# bandpass_40m_v4.net
KiCad netlist of a schematic drawn in EAGLE
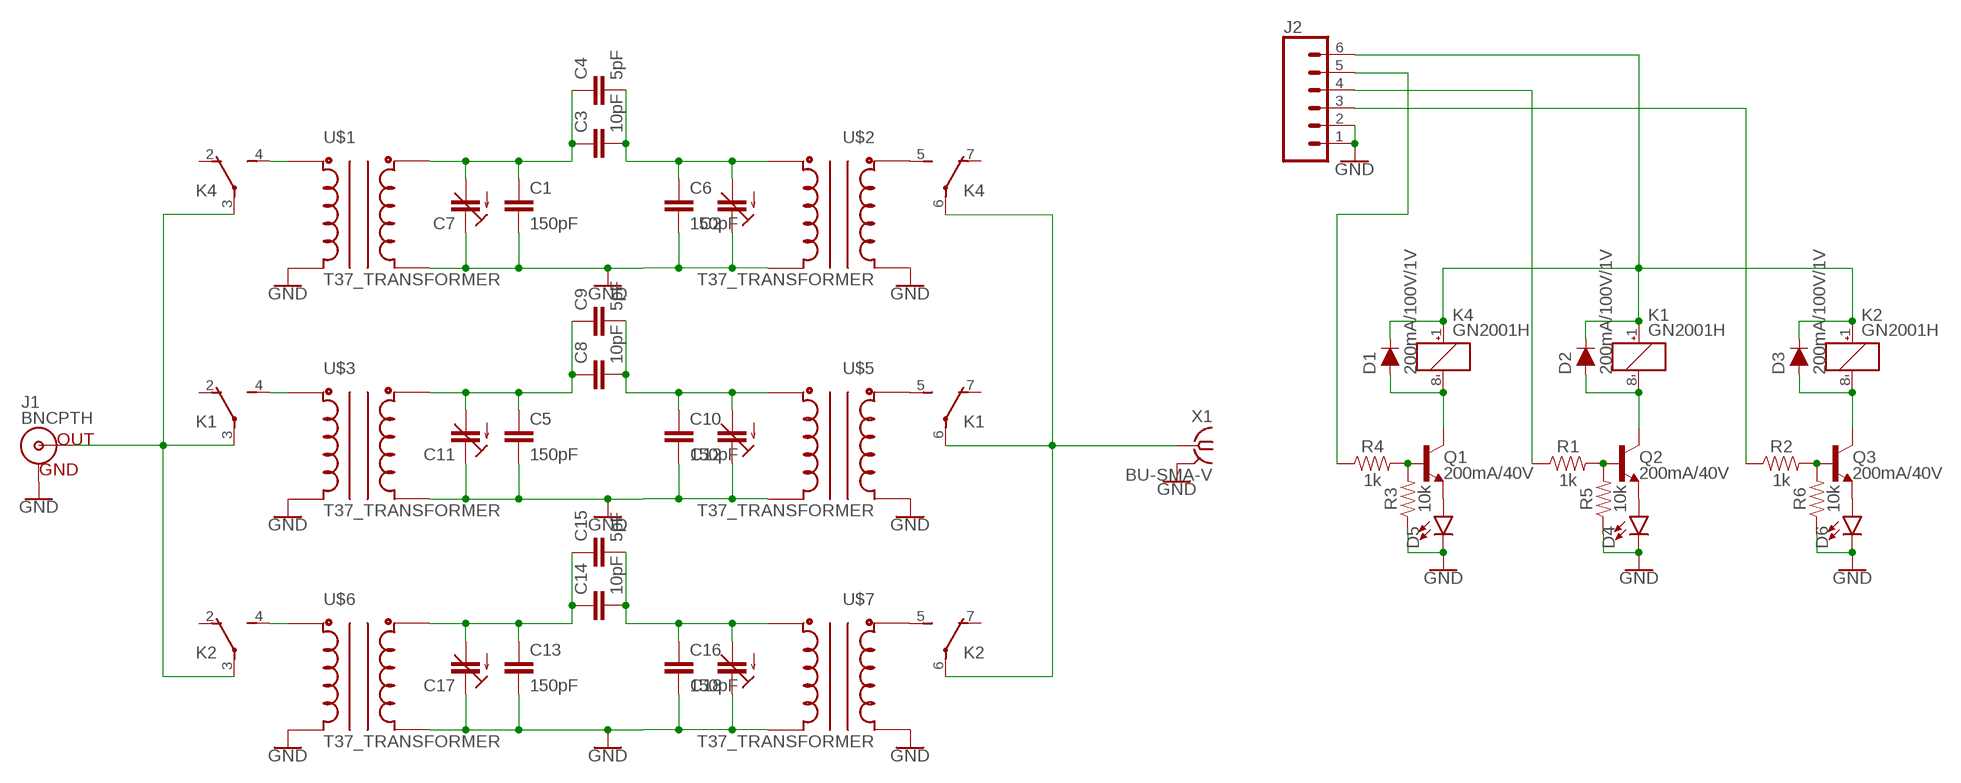
[diagram p0: schematic, sheet 1]

(export (version "E")
  (design (tool "Eeschema 10.0.6"))
  (components
    (comp (ref "C1")
      (value "150pF")
      (footprint "eagle-import:C5B3.5")
      (libsource (lib "eagle-import") (part "C5/3.5"))
    )
    (comp (ref "C2")
      (value "C-TRIMMTZ03")
      (footprint "eagle-import:CTRIMTZ03")
      (libsource (lib "eagle-import") (part "C-TRIMMTZ03"))
    )
    (comp (ref "C3")
      (value "10pF")
      (footprint "eagle-import:C5B3.5")
      (libsource (lib "eagle-import") (part "C5/3.5"))
    )
    (comp (ref "C4")
      (value "5pF")
      (footprint "eagle-import:C5B3.5")
      (libsource (lib "eagle-import") (part "C5/3.5"))
    )
    (comp (ref "C5")
      (value "150pF")
      (footprint "eagle-import:C5B3.5")
      (libsource (lib "eagle-import") (part "C5/3.5"))
    )
    (comp (ref "C6")
      (value "150pF")
      (footprint "eagle-import:C5B3.5")
      (libsource (lib "eagle-import") (part "C5/3.5"))
    )
    (comp (ref "C7")
      (value "C-TRIMMTZ03")
      (footprint "eagle-import:CTRIMTZ03")
      (libsource (lib "eagle-import") (part "C-TRIMMTZ03"))
    )
    (comp (ref "C8")
      (value "10pF")
      (footprint "eagle-import:C5B3.5")
      (libsource (lib "eagle-import") (part "C5/3.5"))
    )
    (comp (ref "C9")
      (value "5pF")
      (footprint "eagle-import:C5B3.5")
      (libsource (lib "eagle-import") (part "C5/3.5"))
    )
    (comp (ref "C10")
      (value "150pF")
      (footprint "eagle-import:C5B3.5")
      (libsource (lib "eagle-import") (part "C5/3.5"))
    )
    (comp (ref "C11")
      (value "C-TRIMMTZ03")
      (footprint "eagle-import:CTRIMTZ03")
      (libsource (lib "eagle-import") (part "C-TRIMMTZ03"))
    )
    (comp (ref "C12")
      (value "C-TRIMMTZ03")
      (footprint "eagle-import:CTRIMTZ03")
      (libsource (lib "eagle-import") (part "C-TRIMMTZ03"))
    )
    (comp (ref "C13")
      (value "150pF")
      (footprint "eagle-import:C5B3.5")
      (libsource (lib "eagle-import") (part "C5/3.5"))
    )
    (comp (ref "C14")
      (value "10pF")
      (footprint "eagle-import:C5B3.5")
      (libsource (lib "eagle-import") (part "C5/3.5"))
    )
    (comp (ref "C15")
      (value "5pF")
      (footprint "eagle-import:C5B3.5")
      (libsource (lib "eagle-import") (part "C5/3.5"))
    )
    (comp (ref "C16")
      (value "150pF")
      (footprint "eagle-import:C5B3.5")
      (libsource (lib "eagle-import") (part "C5/3.5"))
    )
    (comp (ref "C17")
      (value "C-TRIMMTZ03")
      (footprint "eagle-import:CTRIMTZ03")
      (libsource (lib "eagle-import") (part "C-TRIMMTZ03"))
    )
    (comp (ref "C18")
      (value "C-TRIMMTZ03")
      (footprint "eagle-import:CTRIMTZ03")
      (libsource (lib "eagle-import") (part "C-TRIMMTZ03"))
    )
    (comp (ref "D1")
      (value "200mA/100V/1V")
      (footprint "eagle-import:DIODE-1N4148")
      (libsource (lib "eagle-import") (part "DIODE-1N4148"))
    )
    (comp (ref "D2")
      (value "200mA/100V/1V")
      (footprint "eagle-import:DIODE-1N4148")
      (libsource (lib "eagle-import") (part "DIODE-1N4148"))
    )
    (comp (ref "D3")
      (value "200mA/100V/1V")
      (footprint "eagle-import:DIODE-1N4148")
      (libsource (lib "eagle-import") (part "DIODE-1N4148"))
    )
    (comp (ref "D4")
      (value "LED5MM")
      (footprint "eagle-import:LED_5MM")
      (libsource (lib "eagle-import") (part "LED5MM"))
    )
    (comp (ref "D5")
      (value "LED5MM")
      (footprint "eagle-import:LED_5MM")
      (libsource (lib "eagle-import") (part "LED5MM"))
    )
    (comp (ref "D6")
      (value "LED5MM")
      (footprint "eagle-import:LED_5MM")
      (libsource (lib "eagle-import") (part "LED5MM"))
    )
    (comp (ref "J1")
      (value "BNCPTH")
      (footprint "eagle-import:BNC")
      (libsource (lib "eagle-import") (part "BNCPTH"))
    )
    (comp (ref "J2")
      (value "CONN_06LONGPADS")
      (footprint "eagle-import:1X06_LONGPADS")
      (libsource (lib "eagle-import") (part "CONN_06LONGPADS"))
    )
    (comp (ref "K1")
      (value "GN2001H")
      (footprint "eagle-import:GN")
      (libsource (lib "eagle-import") (part "GN?2001H"))
    )
    (comp (ref "K2")
      (value "GN2001H")
      (footprint "eagle-import:GN")
      (libsource (lib "eagle-import") (part "GN?2001H"))
    )
    (comp (ref "K4")
      (value "GN2001H")
      (footprint "eagle-import:GN")
      (libsource (lib "eagle-import") (part "GN?2001H"))
    )
    (comp (ref "Q1")
      (value "200mA/40V")
      (footprint "eagle-import:TO-92")
      (libsource (lib "eagle-import") (part "TRANS_NPN-2N3904"))
    )
    (comp (ref "Q2")
      (value "200mA/40V")
      (footprint "eagle-import:TO-92")
      (libsource (lib "eagle-import") (part "TRANS_NPN-2N3904"))
    )
    (comp (ref "Q3")
      (value "200mA/40V")
      (footprint "eagle-import:TO-92")
      (libsource (lib "eagle-import") (part "TRANS_NPN-2N3904"))
    )
    (comp (ref "R1")
      (value "1k")
      (footprint "eagle-import:AXIAL-0.3")
      (libsource (lib "eagle-import") (part "1KOHM-HORIZ-1/4W-1%"))
    )
    (comp (ref "R2")
      (value "1k")
      (footprint "eagle-import:AXIAL-0.3")
      (libsource (lib "eagle-import") (part "1KOHM-HORIZ-1/4W-1%"))
    )
    (comp (ref "R3")
      (value "10k")
      (footprint "eagle-import:AXIAL-0.3")
      (libsource (lib "eagle-import") (part "1KOHM-HORIZ-1/4W-1%"))
    )
    (comp (ref "R4")
      (value "1k")
      (footprint "eagle-import:AXIAL-0.3")
      (libsource (lib "eagle-import") (part "1KOHM-HORIZ-1/4W-1%"))
    )
    (comp (ref "R5")
      (value "10k")
      (footprint "eagle-import:AXIAL-0.3")
      (libsource (lib "eagle-import") (part "1KOHM-HORIZ-1/4W-1%"))
    )
    (comp (ref "R6")
      (value "10k")
      (footprint "eagle-import:AXIAL-0.3")
      (libsource (lib "eagle-import") (part "1KOHM-HORIZ-1/4W-1%"))
    )
    (comp (ref "U$1")
      (value "T37_TRANSFORMER")
      (footprint "eagle-import:T37_TRANSFORMER")
      (libsource (lib "eagle-import") (part "T37_TRANSFORMER"))
    )
    (comp (ref "U$2")
      (value "T37_TRANSFORMER")
      (footprint "eagle-import:T37_TRANSFORMER")
      (libsource (lib "eagle-import") (part "T37_TRANSFORMER"))
    )
    (comp (ref "U$3")
      (value "T37_TRANSFORMER")
      (footprint "eagle-import:T37_TRANSFORMER")
      (libsource (lib "eagle-import") (part "T37_TRANSFORMER"))
    )
    (comp (ref "U$5")
      (value "T37_TRANSFORMER")
      (footprint "eagle-import:T37_TRANSFORMER")
      (libsource (lib "eagle-import") (part "T37_TRANSFORMER"))
    )
    (comp (ref "U$6")
      (value "T37_TRANSFORMER")
      (footprint "eagle-import:T37_TRANSFORMER")
      (libsource (lib "eagle-import") (part "T37_TRANSFORMER"))
    )
    (comp (ref "U$7")
      (value "T37_TRANSFORMER")
      (footprint "eagle-import:T37_TRANSFORMER")
      (libsource (lib "eagle-import") (part "T37_TRANSFORMER"))
    )
    (comp (ref "X1")
      (value "BU-SMA-V")
      (footprint "eagle-import:BU-SMA-V")
      (libsource (lib "eagle-import") (part "BU-SMA-V"))
    )
  )
  (nets
    (net (code "1") (name "GND") (class "Default")
      (node (ref "C1") (pin "2") (pinfunction "2_2") (pintype "passive"))
      (node (ref "C10") (pin "2") (pinfunction "2_2") (pintype "passive"))
      (node (ref "C11") (pin "1") (pinfunction "E_1") (pintype "passive"))
      (node (ref "C12") (pin "1") (pinfunction "E_1") (pintype "passive"))
      (node (ref "C13") (pin "2") (pinfunction "2_2") (pintype "passive"))
      (node (ref "C16") (pin "2") (pinfunction "2_2") (pintype "passive"))
      (node (ref "C17") (pin "1") (pinfunction "E_1") (pintype "passive"))
      (node (ref "C18") (pin "1") (pinfunction "E_1") (pintype "passive"))
      (node (ref "C2") (pin "1") (pinfunction "E_1") (pintype "passive"))
      (node (ref "C5") (pin "2") (pinfunction "2_2") (pintype "passive"))
      (node (ref "C6") (pin "2") (pinfunction "2_2") (pintype "passive"))
      (node (ref "C7") (pin "1") (pinfunction "E_1") (pintype "passive"))
      (node (ref "D4") (pin "K") (pinfunction "C_K") (pintype "passive"))
      (node (ref "D5") (pin "K") (pinfunction "C_K") (pintype "passive"))
      (node (ref "D6") (pin "K") (pinfunction "C_K") (pintype "passive"))
      (node (ref "J1") (pin "GND") (pinfunction "GND_GND") (pintype "bidirectional"))
      (node (ref "J2") (pin "1") (pinfunction "1_1") (pintype "passive"))
      (node (ref "J2") (pin "2") (pinfunction "2_2") (pintype "passive"))
      (node (ref "R3") (pin "P$1") (pinfunction "1_P$1") (pintype "passive"))
      (node (ref "R5") (pin "P$1") (pinfunction "1_P$1") (pintype "passive"))
      (node (ref "R6") (pin "P$1") (pinfunction "1_P$1") (pintype "passive"))
      (node (ref "U$1") (pin "C1A") (pinfunction "C1A_C1A") (pintype "bidirectional"))
      (node (ref "U$1") (pin "C2A") (pinfunction "C2A_C2A") (pintype "bidirectional"))
      (node (ref "U$2") (pin "C1A") (pinfunction "C1A_C1A") (pintype "bidirectional"))
      (node (ref "U$2") (pin "C2A") (pinfunction "C2A_C2A") (pintype "bidirectional"))
      (node (ref "U$3") (pin "C1A") (pinfunction "C1A_C1A") (pintype "bidirectional"))
      (node (ref "U$3") (pin "C2A") (pinfunction "C2A_C2A") (pintype "bidirectional"))
      (node (ref "U$5") (pin "C1A") (pinfunction "C1A_C1A") (pintype "bidirectional"))
      (node (ref "U$5") (pin "C2A") (pinfunction "C2A_C2A") (pintype "bidirectional"))
      (node (ref "U$6") (pin "C1A") (pinfunction "C1A_C1A") (pintype "bidirectional"))
      (node (ref "U$6") (pin "C2A") (pinfunction "C2A_C2A") (pintype "bidirectional"))
      (node (ref "U$7") (pin "C1A") (pinfunction "C1A_C1A") (pintype "bidirectional"))
      (node (ref "U$7") (pin "C2A") (pinfunction "C2A_C2A") (pintype "bidirectional"))
      (node (ref "X1") (pin "2") (pinfunction "2_2") (pintype "passive"))
      (node (ref "X1") (pin "3") (pinfunction "2_3") (pintype "passive"))
      (node (ref "X1") (pin "4") (pinfunction "2_4") (pintype "passive"))
      (node (ref "X1") (pin "5") (pinfunction "2_5") (pintype "passive"))
    )
    (net (code "2") (name "Net-(C2-A)") (class "Default")
      (node (ref "C2") (pin "2") (pinfunction "A_2") (pintype "passive"))
      (node (ref "C3") (pin "2") (pinfunction "2_2") (pintype "passive"))
      (node (ref "C4") (pin "2") (pinfunction "2_2") (pintype "passive"))
      (node (ref "C6") (pin "1") (pinfunction "1_1") (pintype "passive"))
      (node (ref "U$2") (pin "C2B") (pinfunction "C2B_C2B") (pintype "bidirectional"))
    )
    (net (code "3") (name "Net-(C7-A)") (class "Default")
      (node (ref "C1") (pin "1") (pinfunction "1_1") (pintype "passive"))
      (node (ref "C3") (pin "1") (pinfunction "1_1") (pintype "passive"))
      (node (ref "C4") (pin "1") (pinfunction "1_1") (pintype "passive"))
      (node (ref "C7") (pin "2") (pinfunction "A_2") (pintype "passive"))
      (node (ref "U$1") (pin "C2B") (pinfunction "C2B_C2B") (pintype "bidirectional"))
    )
    (net (code "4") (name "Net-(C11-A)") (class "Default")
      (node (ref "C11") (pin "2") (pinfunction "A_2") (pintype "passive"))
      (node (ref "C5") (pin "1") (pinfunction "1_1") (pintype "passive"))
      (node (ref "C8") (pin "1") (pinfunction "1_1") (pintype "passive"))
      (node (ref "C9") (pin "1") (pinfunction "1_1") (pintype "passive"))
      (node (ref "U$3") (pin "C2B") (pinfunction "C2B_C2B") (pintype "bidirectional"))
    )
    (net (code "5") (name "Net-(C12-A)") (class "Default")
      (node (ref "C10") (pin "1") (pinfunction "1_1") (pintype "passive"))
      (node (ref "C12") (pin "2") (pinfunction "A_2") (pintype "passive"))
      (node (ref "C8") (pin "2") (pinfunction "2_2") (pintype "passive"))
      (node (ref "C9") (pin "2") (pinfunction "2_2") (pintype "passive"))
      (node (ref "U$5") (pin "C2B") (pinfunction "C2B_C2B") (pintype "bidirectional"))
    )
    (net (code "6") (name "Net-(C17-A)") (class "Default")
      (node (ref "C13") (pin "1") (pinfunction "1_1") (pintype "passive"))
      (node (ref "C14") (pin "1") (pinfunction "1_1") (pintype "passive"))
      (node (ref "C15") (pin "1") (pinfunction "1_1") (pintype "passive"))
      (node (ref "C17") (pin "2") (pinfunction "A_2") (pintype "passive"))
      (node (ref "U$6") (pin "C2B") (pinfunction "C2B_C2B") (pintype "bidirectional"))
    )
    (net (code "7") (name "Net-(C18-A)") (class "Default")
      (node (ref "C14") (pin "2") (pinfunction "2_2") (pintype "passive"))
      (node (ref "C15") (pin "2") (pinfunction "2_2") (pintype "passive"))
      (node (ref "C16") (pin "1") (pinfunction "1_1") (pintype "passive"))
      (node (ref "C18") (pin "2") (pinfunction "A_2") (pintype "passive"))
      (node (ref "U$7") (pin "C2B") (pinfunction "C2B_C2B") (pintype "bidirectional"))
    )
    (net (code "8") (name "Net-(J1-OUT)") (class "Default")
      (node (ref "J1") (pin "S") (pinfunction "OUT_S") (pintype "bidirectional"))
      (node (ref "K1") (pin "3") (pinfunction "P_3") (pintype "passive"))
      (node (ref "K2") (pin "3") (pinfunction "P_3") (pintype "passive"))
      (node (ref "K4") (pin "3") (pinfunction "P_3") (pintype "passive"))
    )
    (net (code "9") (name "Net-(K1A-+)") (class "Default")
      (node (ref "D1") (pin "C") (pinfunction "C_C") (pintype "passive"))
      (node (ref "D2") (pin "C") (pinfunction "C_C") (pintype "passive"))
      (node (ref "D3") (pin "C") (pinfunction "C_C") (pintype "passive"))
      (node (ref "J2") (pin "6") (pinfunction "6_6") (pintype "passive"))
      (node (ref "K1") (pin "1") (pinfunction "+_1") (pintype "passive"))
      (node (ref "K2") (pin "1") (pinfunction "+_1") (pintype "passive"))
      (node (ref "K4") (pin "1") (pinfunction "+_1") (pintype "passive"))
    )
    (net (code "10") (name "Net-(K1A--)") (class "Default")
      (node (ref "D2") (pin "A") (pinfunction "A_A") (pintype "passive"))
      (node (ref "K1") (pin "8") (pinfunction "-_8") (pintype "passive"))
      (node (ref "Q2") (pin "3") (pinfunction "C_3") (pintype "passive"))
    )
    (net (code "11") (name "Net-(K1B-S)") (class "Default")
      (node (ref "K1") (pin "4") (pinfunction "S_4") (pintype "passive"))
      (node (ref "U$3") (pin "C1B") (pinfunction "C1B_C1B") (pintype "bidirectional"))
    )
    (net (code "12") (name "Net-(K1C-P)") (class "Default")
      (node (ref "K1") (pin "6") (pinfunction "P_6") (pintype "passive"))
      (node (ref "K2") (pin "6") (pinfunction "P_6") (pintype "passive"))
      (node (ref "K4") (pin "6") (pinfunction "P_6") (pintype "passive"))
      (node (ref "X1") (pin "1") (pinfunction "1_1") (pintype "passive"))
    )
    (net (code "13") (name "Net-(K1C-S)") (class "Default")
      (node (ref "K1") (pin "5") (pinfunction "S_5") (pintype "passive"))
      (node (ref "U$5") (pin "C1B") (pinfunction "C1B_C1B") (pintype "bidirectional"))
    )
    (net (code "14") (name "Net-(K2A--)") (class "Default")
      (node (ref "D3") (pin "A") (pinfunction "A_A") (pintype "passive"))
      (node (ref "K2") (pin "8") (pinfunction "-_8") (pintype "passive"))
      (node (ref "Q3") (pin "3") (pinfunction "C_3") (pintype "passive"))
    )
    (net (code "15") (name "Net-(K2B-S)") (class "Default")
      (node (ref "K2") (pin "4") (pinfunction "S_4") (pintype "passive"))
      (node (ref "U$6") (pin "C1B") (pinfunction "C1B_C1B") (pintype "bidirectional"))
    )
    (net (code "16") (name "Net-(K2C-S)") (class "Default")
      (node (ref "K2") (pin "5") (pinfunction "S_5") (pintype "passive"))
      (node (ref "U$7") (pin "C1B") (pinfunction "C1B_C1B") (pintype "bidirectional"))
    )
    (net (code "17") (name "Net-(K4A--)") (class "Default")
      (node (ref "D1") (pin "A") (pinfunction "A_A") (pintype "passive"))
      (node (ref "K4") (pin "8") (pinfunction "-_8") (pintype "passive"))
      (node (ref "Q1") (pin "3") (pinfunction "C_3") (pintype "passive"))
    )
    (net (code "18") (name "Net-(K4B-S)") (class "Default")
      (node (ref "K4") (pin "4") (pinfunction "S_4") (pintype "passive"))
      (node (ref "U$1") (pin "C1B") (pinfunction "C1B_C1B") (pintype "bidirectional"))
    )
    (net (code "19") (name "Net-(K4C-S)") (class "Default")
      (node (ref "K4") (pin "5") (pinfunction "S_5") (pintype "passive"))
      (node (ref "U$2") (pin "C1B") (pinfunction "C1B_C1B") (pintype "bidirectional"))
    )
    (net (code "20") (name "Net-(Q1-B)") (class "Default")
      (node (ref "Q1") (pin "2") (pinfunction "B_2") (pintype "passive"))
      (node (ref "R3") (pin "P$2") (pinfunction "2_P$2") (pintype "passive"))
      (node (ref "R4") (pin "P$2") (pinfunction "2_P$2") (pintype "passive"))
    )
    (net (code "21") (name "Net-(Q1-E)") (class "Default")
      (node (ref "D5") (pin "A") (pinfunction "A_A") (pintype "passive"))
      (node (ref "Q1") (pin "1") (pinfunction "E_1") (pintype "passive"))
    )
    (net (code "22") (name "Net-(Q2-B)") (class "Default")
      (node (ref "Q2") (pin "2") (pinfunction "B_2") (pintype "passive"))
      (node (ref "R1") (pin "P$2") (pinfunction "2_P$2") (pintype "passive"))
      (node (ref "R5") (pin "P$2") (pinfunction "2_P$2") (pintype "passive"))
    )
    (net (code "23") (name "Net-(Q2-E)") (class "Default")
      (node (ref "D4") (pin "A") (pinfunction "A_A") (pintype "passive"))
      (node (ref "Q2") (pin "1") (pinfunction "E_1") (pintype "passive"))
    )
    (net (code "24") (name "Net-(Q3-B)") (class "Default")
      (node (ref "Q3") (pin "2") (pinfunction "B_2") (pintype "passive"))
      (node (ref "R2") (pin "P$2") (pinfunction "2_P$2") (pintype "passive"))
      (node (ref "R6") (pin "P$2") (pinfunction "2_P$2") (pintype "passive"))
    )
    (net (code "25") (name "Net-(Q3-E)") (class "Default")
      (node (ref "D6") (pin "A") (pinfunction "A_A") (pintype "passive"))
      (node (ref "Q3") (pin "1") (pinfunction "E_1") (pintype "passive"))
    )
    (net (code "26") (name "Net-(R1-1)") (class "Default")
      (node (ref "J2") (pin "4") (pinfunction "4_4") (pintype "passive"))
      (node (ref "R1") (pin "P$1") (pinfunction "1_P$1") (pintype "passive"))
    )
    (net (code "27") (name "Net-(R2-1)") (class "Default")
      (node (ref "J2") (pin "3") (pinfunction "3_3") (pintype "passive"))
      (node (ref "R2") (pin "P$1") (pinfunction "1_P$1") (pintype "passive"))
    )
    (net (code "28") (name "Net-(R4-1)") (class "Default")
      (node (ref "J2") (pin "5") (pinfunction "5_5") (pintype "passive"))
      (node (ref "R4") (pin "P$1") (pinfunction "1_P$1") (pintype "passive"))
    )
    (net (code "29") (name "unconnected-(K1B-O-Pad2)") (class "Default")
      (node (ref "K1") (pin "2") (pinfunction "O_2") (pintype "passive"))
    )
    (net (code "30") (name "unconnected-(K1C-O-Pad7)") (class "Default")
      (node (ref "K1") (pin "7") (pinfunction "O_7") (pintype "passive"))
    )
    (net (code "31") (name "unconnected-(K2B-O-Pad2)") (class "Default")
      (node (ref "K2") (pin "2") (pinfunction "O_2") (pintype "passive"))
    )
    (net (code "32") (name "unconnected-(K2C-O-Pad7)") (class "Default")
      (node (ref "K2") (pin "7") (pinfunction "O_7") (pintype "passive"))
    )
    (net (code "33") (name "unconnected-(K4B-O-Pad2)") (class "Default")
      (node (ref "K4") (pin "2") (pinfunction "O_2") (pintype "passive"))
    )
    (net (code "34") (name "unconnected-(K4C-O-Pad7)") (class "Default")
      (node (ref "K4") (pin "7") (pinfunction "O_7") (pintype "passive"))
    )
  )
)
